# ADC_AD7761BSTZ.net
KiCad netlist of a schematic drawn in EAGLE
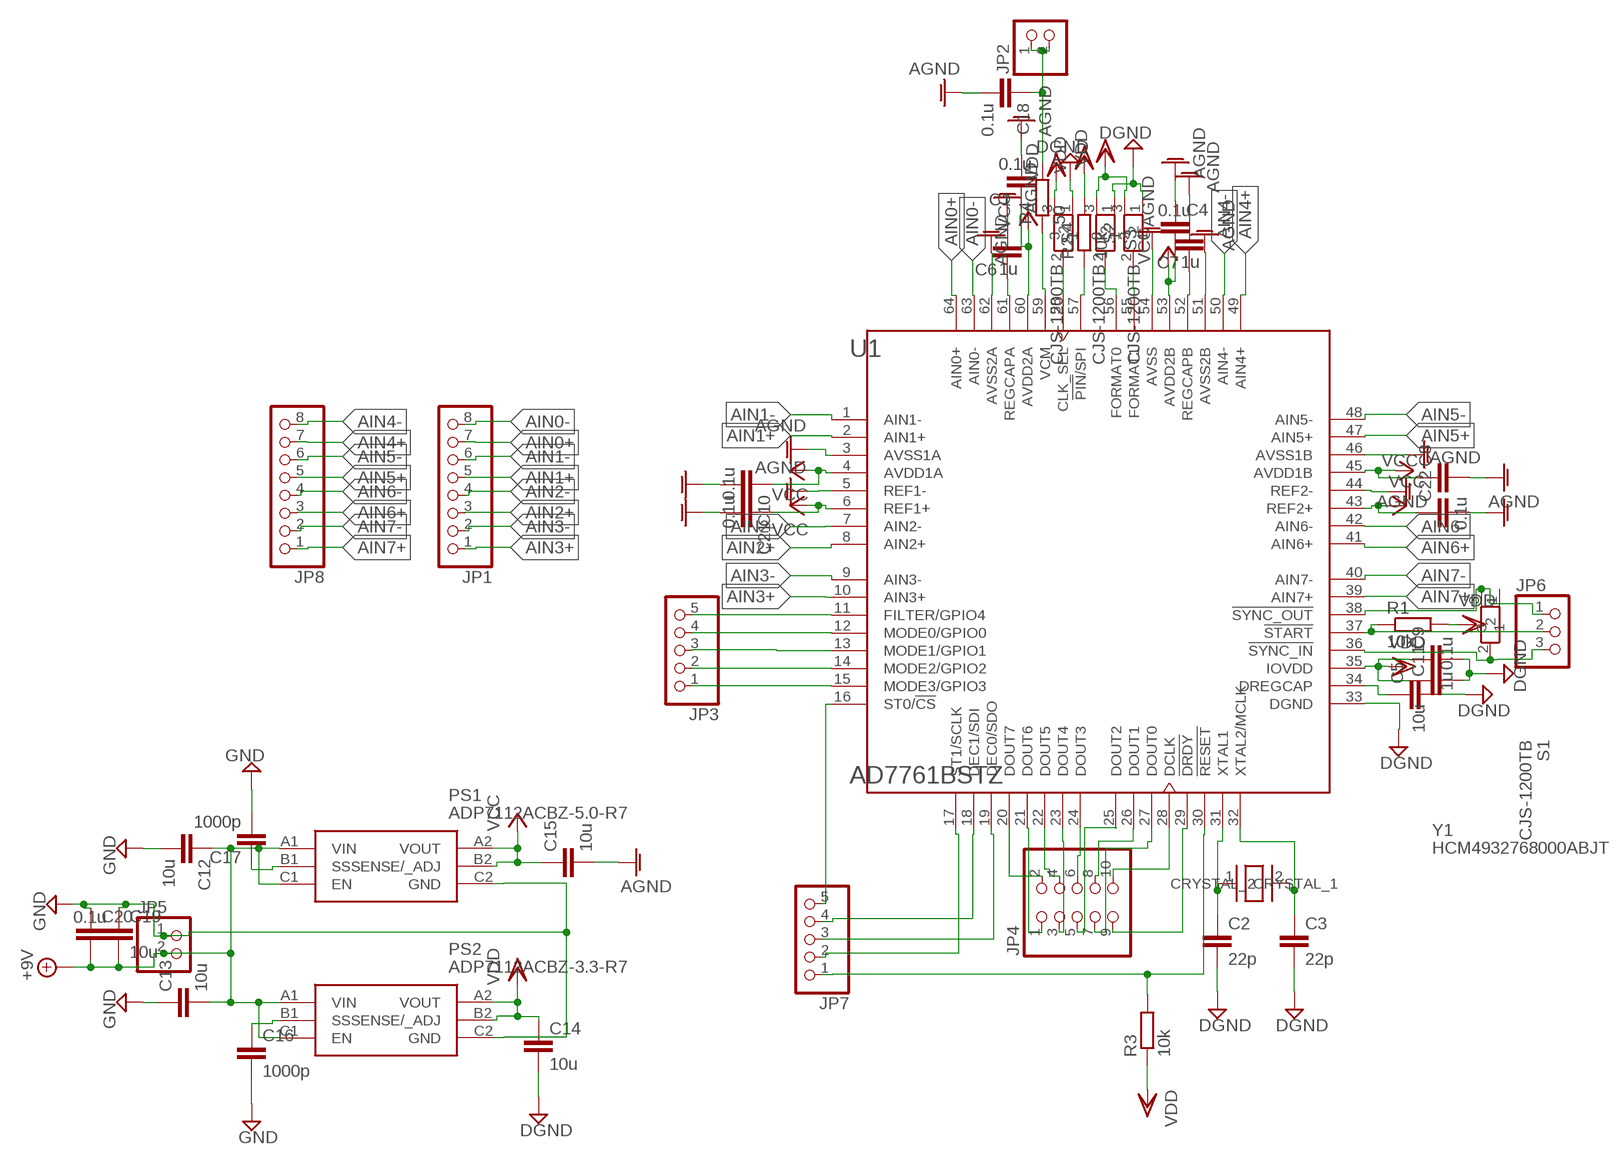
[diagram p0: schematic, sheet 1]

(export (version "E")
  (design (tool "Eeschema 10.0.6"))
  (components
    (comp (ref "C1")
      (value "0.1u")
      (footprint "eagle-import:C1608")
      (libsource (lib "eagle-import") (part "C-EUC1608"))
    )
    (comp (ref "C2")
      (value "22p")
      (footprint "eagle-import:C1608")
      (libsource (lib "eagle-import") (part "C-EUC1608"))
    )
    (comp (ref "C3")
      (value "22p")
      (footprint "eagle-import:C1608")
      (libsource (lib "eagle-import") (part "C-EUC1608"))
    )
    (comp (ref "C4")
      (value "0.1u")
      (footprint "eagle-import:C1608")
      (libsource (lib "eagle-import") (part "C-EUC1608"))
    )
    (comp (ref "C5")
      (value "10u")
      (footprint "eagle-import:C2012")
      (libsource (lib "eagle-import") (part "C-EUC2012"))
    )
    (comp (ref "C6")
      (value "1u")
      (footprint "eagle-import:C1608")
      (libsource (lib "eagle-import") (part "C-EUC1608"))
    )
    (comp (ref "C7")
      (value "1u")
      (footprint "eagle-import:C1608")
      (libsource (lib "eagle-import") (part "C-EUC1608"))
    )
    (comp (ref "C8")
      (value "0.1u")
      (footprint "eagle-import:C1608")
      (libsource (lib "eagle-import") (part "C-EUC1608"))
    )
    (comp (ref "C9")
      (value "0.1u")
      (footprint "eagle-import:C1608")
      (libsource (lib "eagle-import") (part "C-EUC1608"))
    )
    (comp (ref "C10")
      (value "0.1u")
      (footprint "eagle-import:C1608")
      (libsource (lib "eagle-import") (part "C-EUC1608"))
    )
    (comp (ref "C11")
      (value "1u")
      (footprint "eagle-import:C1608")
      (libsource (lib "eagle-import") (part "C-EUC1608"))
    )
    (comp (ref "C12")
      (value "10u")
      (footprint "eagle-import:C2012")
      (libsource (lib "eagle-import") (part "C-EUC2012"))
    )
    (comp (ref "C13")
      (value "10u")
      (footprint "eagle-import:C2012")
      (libsource (lib "eagle-import") (part "C-EUC2012"))
    )
    (comp (ref "C14")
      (value "10u")
      (footprint "eagle-import:C2012")
      (libsource (lib "eagle-import") (part "C-EUC2012"))
    )
    (comp (ref "C15")
      (value "10u")
      (footprint "eagle-import:C2012")
      (libsource (lib "eagle-import") (part "C-EUC2012"))
    )
    (comp (ref "C16")
      (value "1000p")
      (footprint "eagle-import:C1608")
      (libsource (lib "eagle-import") (part "C-EUC1608"))
    )
    (comp (ref "C17")
      (value "1000p")
      (footprint "eagle-import:C1608")
      (libsource (lib "eagle-import") (part "C-EUC1608"))
    )
    (comp (ref "C18")
      (value "0.1u")
      (footprint "eagle-import:C1608")
      (libsource (lib "eagle-import") (part "C-EUC1608"))
    )
    (comp (ref "C19")
      (value "10u")
      (footprint "eagle-import:C2012")
      (libsource (lib "eagle-import") (part "C-EUC2012"))
    )
    (comp (ref "C20")
      (value "0.1u")
      (footprint "eagle-import:C1608")
      (libsource (lib "eagle-import") (part "C-EUC1608"))
    )
    (comp (ref "C21")
      (value "0.1u")
      (footprint "eagle-import:C1608")
      (libsource (lib "eagle-import") (part "C-EUC1608"))
    )
    (comp (ref "C22")
      (value "0.1u")
      (footprint "eagle-import:C1608")
      (libsource (lib "eagle-import") (part "C-EUC1608"))
    )
    (comp (ref "JP1")
      (value "PINHD-1X8")
      (footprint "eagle-import:1X08")
      (libsource (lib "eagle-import") (part "PINHD-1X8"))
    )
    (comp (ref "JP2")
      (value "PINHD-1X2")
      (footprint "eagle-import:1X02")
      (libsource (lib "eagle-import") (part "PINHD-1X2"))
    )
    (comp (ref "JP3")
      (value "PINHD-1X5")
      (footprint "eagle-import:1X05")
      (libsource (lib "eagle-import") (part "PINHD-1X5"))
    )
    (comp (ref "JP4")
      (value "PINHD-2X5")
      (footprint "eagle-import:2X05")
      (libsource (lib "eagle-import") (part "PINHD-2X5"))
    )
    (comp (ref "JP5")
      (value "PINHD-1X2")
      (footprint "eagle-import:1X02")
      (libsource (lib "eagle-import") (part "PINHD-1X2"))
    )
    (comp (ref "JP6")
      (value "PINHD-1X3")
      (footprint "eagle-import:1X03")
      (libsource (lib "eagle-import") (part "PINHD-1X3"))
    )
    (comp (ref "JP7")
      (value "PINHD-1X5")
      (footprint "eagle-import:1X05")
      (libsource (lib "eagle-import") (part "PINHD-1X5"))
    )
    (comp (ref "JP8")
      (value "PINHD-1X8")
      (footprint "eagle-import:1X08")
      (libsource (lib "eagle-import") (part "PINHD-1X8"))
    )
    (comp (ref "PS1")
      (value "ADP7112ACBZ-5.0-R7")
      (footprint "eagle-import:BGA6C40P2X3_95X116X56")
      (fields
        (field (name "ARROW_PART_NUMBER") "ADP7112ACBZ-3.3-R7")
        (field (name "MOUSER_PART_NUMBER") "584-ADP7112ACBZ3.3R7")
      )
      (libsource (lib "eagle-import") (part "ADP7112ACBZ-3.3-R7"))
    )
    (comp (ref "PS2")
      (value "ADP7112ACBZ-3.3-R7")
      (footprint "eagle-import:BGA6C40P2X3_95X116X56")
      (fields (field (name "MOUSER_PART_NUMBER") "584-ADP7112ACBZ3.3R7"))
      (libsource (lib "eagle-import") (part "ADP7112ACBZ-3.3-R7"))
    )
    (comp (ref "R1")
      (value "10k")
      (footprint "eagle-import:R0603")
      (libsource (lib "eagle-import") (part "R-EU_R0603"))
    )
    (comp (ref "R2")
      (value "10k")
      (footprint "eagle-import:R0603")
      (libsource (lib "eagle-import") (part "R-EU_R0603"))
    )
    (comp (ref "R3")
      (value "10k")
      (footprint "eagle-import:R0603")
      (libsource (lib "eagle-import") (part "R-EU_R0603"))
    )
    (comp (ref "R4")
      (value "50")
      (footprint "eagle-import:R0603")
      (libsource (lib "eagle-import") (part "R-EU_R0603"))
    )
    (comp (ref "S1")
      (value "CJS-1200TB")
      (footprint "eagle-import:B-TYPE")
      (libsource (lib "eagle-import") (part "CJS-1200TB"))
    )
    (comp (ref "S2")
      (value "CJS-1200TB")
      (footprint "eagle-import:B-TYPE")
      (libsource (lib "eagle-import") (part "CJS-1200TB"))
    )
    (comp (ref "S3")
      (value "CJS-1200TB")
      (footprint "eagle-import:B-TYPE")
      (libsource (lib "eagle-import") (part "CJS-1200TB"))
    )
    (comp (ref "S4")
      (value "CJS-1200TB")
      (footprint "eagle-import:B-TYPE")
      (libsource (lib "eagle-import") (part "CJS-1200TB"))
    )
    (comp (ref "U1")
      (value "AD7761BSTZ")
      (footprint "eagle-import:QFP50P1200X1200X160-64N")
      (fields (field (name "MF") "Analog Devices"))
      (libsource (lib "eagle-import") (part "AD7761BSTZ"))
    )
    (comp (ref "Y1")
      (value "HCM4932768000ABJT")
      (footprint "eagle-import:HCM4932768000ABJT")
      (fields (field (name "MOUSER_PART_NUMBER") "695-HCM49-327-U"))
      (libsource (lib "eagle-import") (part "HCM4932768000ABJT"))
    )
  )
  (nets
    (net (code "1") (name "+9V") (class "Default")
      (node (ref "C12") (pin "1") (pinfunction "1_1") (pintype "passive"))
      (node (ref "C13") (pin "2") (pinfunction "2_2") (pintype "passive"))
      (node (ref "C19") (pin "2") (pinfunction "2_2") (pintype "passive"))
      (node (ref "C20") (pin "2") (pinfunction "2_2") (pintype "passive"))
      (node (ref "JP5") (pin "2") (pinfunction "2_2") (pintype "passive"))
      (node (ref "PS1") (pin "A1") (pinfunction "VIN_A1") (pintype "bidirectional"))
      (node (ref "PS1") (pin "C1") (pinfunction "EN_C1") (pintype "bidirectional"))
      (node (ref "PS2") (pin "A1") (pinfunction "VIN_A1") (pintype "bidirectional"))
      (node (ref "PS2") (pin "C1") (pinfunction "EN_C1") (pintype "bidirectional"))
    )
    (net (code "2") (name "AGND") (class "Default")
      (node (ref "C1") (pin "2") (pinfunction "2_2") (pintype "passive"))
      (node (ref "C10") (pin "2") (pinfunction "2_2") (pintype "passive"))
      (node (ref "C15") (pin "2") (pinfunction "2_2") (pintype "passive"))
      (node (ref "C18") (pin "2") (pinfunction "2_2") (pintype "passive"))
      (node (ref "C21") (pin "2") (pinfunction "2_2") (pintype "passive"))
      (node (ref "C22") (pin "2") (pinfunction "2_2") (pintype "passive"))
      (node (ref "C4") (pin "1") (pinfunction "1_1") (pintype "passive"))
      (node (ref "C6") (pin "2") (pinfunction "2_2") (pintype "passive"))
      (node (ref "C7") (pin "2") (pinfunction "2_2") (pintype "passive"))
      (node (ref "C8") (pin "2") (pinfunction "2_2") (pintype "passive"))
      (node (ref "U1") (pin "3") (pinfunction "AVSS1A_3") (pintype "power_in"))
      (node (ref "U1") (pin "44") (pinfunction "REF2-_44") (pintype "input"))
      (node (ref "U1") (pin "46") (pinfunction "AVSS1B_46") (pintype "power_in"))
      (node (ref "U1") (pin "5") (pinfunction "REF1-_5") (pintype "input"))
      (node (ref "U1") (pin "51") (pinfunction "AVSS2B_51") (pintype "power_in"))
      (node (ref "U1") (pin "54") (pinfunction "AVSS_54") (pintype "power_in"))
      (node (ref "U1") (pin "62") (pinfunction "AVSS2A_62") (pintype "power_in"))
    )
    (net (code "3") (name "AIN0+") (class "Default")
      (node (ref "JP1") (pin "7") (pinfunction "7_7") (pintype "passive"))
      (node (ref "U1") (pin "64") (pinfunction "AIN0+_64") (pintype "input"))
    )
    (net (code "4") (name "AIN0-") (class "Default")
      (node (ref "JP1") (pin "8") (pinfunction "8_8") (pintype "passive"))
      (node (ref "U1") (pin "63") (pinfunction "AIN0-_63") (pintype "input"))
    )
    (net (code "5") (name "AIN1+") (class "Default")
      (node (ref "JP1") (pin "5") (pinfunction "5_5") (pintype "passive"))
      (node (ref "U1") (pin "2") (pinfunction "AIN1+_2") (pintype "input"))
    )
    (net (code "6") (name "AIN1-") (class "Default")
      (node (ref "JP1") (pin "6") (pinfunction "6_6") (pintype "passive"))
      (node (ref "U1") (pin "1") (pinfunction "AIN1-_1") (pintype "input"))
    )
    (net (code "7") (name "AIN2+") (class "Default")
      (node (ref "JP1") (pin "3") (pinfunction "3_3") (pintype "passive"))
      (node (ref "U1") (pin "8") (pinfunction "AIN2+_8") (pintype "input"))
    )
    (net (code "8") (name "AIN2-") (class "Default")
      (node (ref "JP1") (pin "4") (pinfunction "4_4") (pintype "passive"))
      (node (ref "U1") (pin "7") (pinfunction "AIN2-_7") (pintype "input"))
    )
    (net (code "9") (name "AIN3+") (class "Default")
      (node (ref "JP1") (pin "1") (pinfunction "1_1") (pintype "passive"))
      (node (ref "U1") (pin "10") (pinfunction "AIN3+_10") (pintype "input"))
    )
    (net (code "10") (name "AIN3-") (class "Default")
      (node (ref "JP1") (pin "2") (pinfunction "2_2") (pintype "passive"))
      (node (ref "U1") (pin "9") (pinfunction "AIN3-_9") (pintype "input"))
    )
    (net (code "11") (name "AIN4+") (class "Default")
      (node (ref "JP8") (pin "7") (pinfunction "7_7") (pintype "passive"))
      (node (ref "U1") (pin "49") (pinfunction "AIN4+_49") (pintype "input"))
    )
    (net (code "12") (name "AIN4-") (class "Default")
      (node (ref "JP8") (pin "8") (pinfunction "8_8") (pintype "passive"))
      (node (ref "U1") (pin "50") (pinfunction "AIN4-_50") (pintype "input"))
    )
    (net (code "13") (name "AIN5+") (class "Default")
      (node (ref "JP8") (pin "5") (pinfunction "5_5") (pintype "passive"))
      (node (ref "U1") (pin "47") (pinfunction "AIN5+_47") (pintype "input"))
    )
    (net (code "14") (name "AIN5-") (class "Default")
      (node (ref "JP8") (pin "6") (pinfunction "6_6") (pintype "passive"))
      (node (ref "U1") (pin "48") (pinfunction "AIN5-_48") (pintype "input"))
    )
    (net (code "15") (name "AIN6+") (class "Default")
      (node (ref "JP8") (pin "3") (pinfunction "3_3") (pintype "passive"))
      (node (ref "U1") (pin "41") (pinfunction "AIN6+_41") (pintype "input"))
    )
    (net (code "16") (name "AIN6-") (class "Default")
      (node (ref "JP8") (pin "4") (pinfunction "4_4") (pintype "passive"))
      (node (ref "U1") (pin "42") (pinfunction "AIN6-_42") (pintype "input"))
    )
    (net (code "17") (name "AIN7+") (class "Default")
      (node (ref "JP8") (pin "1") (pinfunction "1_1") (pintype "passive"))
      (node (ref "U1") (pin "39") (pinfunction "AIN7+_39") (pintype "input"))
    )
    (net (code "18") (name "AIN7-") (class "Default")
      (node (ref "JP8") (pin "2") (pinfunction "2_2") (pintype "passive"))
      (node (ref "U1") (pin "40") (pinfunction "AIN7-_40") (pintype "input"))
    )
    (net (code "19") (name "DGND") (class "Default")
      (node (ref "C11") (pin "2") (pinfunction "2_2") (pintype "passive"))
      (node (ref "C14") (pin "2") (pinfunction "2_2") (pintype "passive"))
      (node (ref "C2") (pin "2") (pinfunction "2_2") (pintype "passive"))
      (node (ref "C3") (pin "2") (pinfunction "2_2") (pintype "passive"))
      (node (ref "C5") (pin "2") (pinfunction "2_2") (pintype "passive"))
      (node (ref "C9") (pin "2") (pinfunction "2_2") (pintype "passive"))
      (node (ref "S2") (pin "1") (pinfunction "1_1") (pintype "bidirectional"))
      (node (ref "S3") (pin "1") (pinfunction "1_1") (pintype "bidirectional"))
      (node (ref "S4") (pin "1") (pinfunction "1_1") (pintype "bidirectional"))
      (node (ref "U1") (pin "33") (pinfunction "DGND_33") (pintype "power_in"))
    )
    (net (code "20") (name "GND") (class "Default")
      (node (ref "C12") (pin "2") (pinfunction "2_2") (pintype "passive"))
      (node (ref "C13") (pin "1") (pinfunction "1_1") (pintype "passive"))
      (node (ref "C16") (pin "2") (pinfunction "2_2") (pintype "passive"))
      (node (ref "C17") (pin "2") (pinfunction "2_2") (pintype "passive"))
      (node (ref "C19") (pin "1") (pinfunction "1_1") (pintype "passive"))
      (node (ref "C20") (pin "1") (pinfunction "1_1") (pintype "passive"))
      (node (ref "JP5") (pin "1") (pinfunction "1_1") (pintype "passive"))
      (node (ref "PS1") (pin "C2") (pinfunction "GND_C2") (pintype "bidirectional"))
      (node (ref "PS2") (pin "C2") (pinfunction "GND_C2") (pintype "bidirectional"))
    )
    (net (code "21") (name "Net-(C18-Pad1)") (class "Default")
      (node (ref "C18") (pin "1") (pinfunction "1_1") (pintype "passive"))
      (node (ref "JP2") (pin "1") (pinfunction "1_1") (pintype "passive"))
      (node (ref "JP2") (pin "2") (pinfunction "2_2") (pintype "passive"))
      (node (ref "R4") (pin "2") (pinfunction "2_2") (pintype "passive"))
    )
    (net (code "22") (name "Net-(PS1-SS)") (class "Default")
      (node (ref "C17") (pin "1") (pinfunction "1_1") (pintype "passive"))
      (node (ref "PS1") (pin "B1") (pinfunction "SS_B1") (pintype "bidirectional"))
    )
    (net (code "23") (name "Net-(PS2-SS)") (class "Default")
      (node (ref "C16") (pin "1") (pinfunction "1_1") (pintype "passive"))
      (node (ref "PS2") (pin "B1") (pinfunction "SS_B1") (pintype "bidirectional"))
    )
    (net (code "24") (name "Net-(U1-CLK_SEL)") (class "Default")
      (node (ref "S4") (pin "2") (pinfunction "2_2") (pintype "bidirectional"))
      (node (ref "U1") (pin "58") (pinfunction "CLK_SEL_58") (pintype "input"))
    )
    (net (code "25") (name "Net-(U1-DCLK)") (class "Default")
      (node (ref "JP4") (pin "10") (pinfunction "10_10") (pintype "passive"))
      (node (ref "U1") (pin "28") (pinfunction "DCLK_28") (pintype "output"))
    )
    (net (code "26") (name "Net-(U1-DEC0{slash}SDO)") (class "Default")
      (node (ref "JP7") (pin "3") (pinfunction "3_3") (pintype "passive"))
      (node (ref "U1") (pin "19") (pinfunction "DEC0/SDO_19") (pintype "bidirectional"))
    )
    (net (code "27") (name "Net-(U1-DEC1{slash}SDI)") (class "Default")
      (node (ref "JP7") (pin "4") (pinfunction "4_4") (pintype "passive"))
      (node (ref "U1") (pin "18") (pinfunction "DEC1/SDI_18") (pintype "input"))
    )
    (net (code "28") (name "Net-(U1-DOUT0)") (class "Default")
      (node (ref "JP4") (pin "7") (pinfunction "7_7") (pintype "passive"))
      (node (ref "U1") (pin "27") (pinfunction "DOUT0_27") (pintype "output"))
    )
    (net (code "29") (name "Net-(U1-DOUT1)") (class "Default")
      (node (ref "JP4") (pin "8") (pinfunction "8_8") (pintype "passive"))
      (node (ref "U1") (pin "26") (pinfunction "DOUT1_26") (pintype "output"))
    )
    (net (code "30") (name "Net-(U1-DOUT2)") (class "Default")
      (node (ref "JP4") (pin "5") (pinfunction "5_5") (pintype "passive"))
      (node (ref "U1") (pin "25") (pinfunction "DOUT2_25") (pintype "output"))
    )
    (net (code "31") (name "Net-(U1-DOUT3)") (class "Default")
      (node (ref "JP4") (pin "6") (pinfunction "6_6") (pintype "passive"))
      (node (ref "U1") (pin "24") (pinfunction "DOUT3_24") (pintype "output"))
    )
    (net (code "32") (name "Net-(U1-DOUT4)") (class "Default")
      (node (ref "JP4") (pin "3") (pinfunction "3_3") (pintype "passive"))
      (node (ref "U1") (pin "23") (pinfunction "DOUT4_23") (pintype "output"))
    )
    (net (code "33") (name "Net-(U1-DOUT5)") (class "Default")
      (node (ref "JP4") (pin "4") (pinfunction "4_4") (pintype "passive"))
      (node (ref "U1") (pin "22") (pinfunction "DOUT5_22") (pintype "output"))
    )
    (net (code "34") (name "Net-(U1-DOUT6)") (class "Default")
      (node (ref "JP4") (pin "1") (pinfunction "1_1") (pintype "passive"))
      (node (ref "U1") (pin "21") (pinfunction "DOUT6_21") (pintype "output"))
    )
    (net (code "35") (name "Net-(U1-DOUT7)") (class "Default")
      (node (ref "JP4") (pin "2") (pinfunction "2_2") (pintype "passive"))
      (node (ref "U1") (pin "20") (pinfunction "DOUT7_20") (pintype "output"))
    )
    (net (code "36") (name "Net-(U1-DREGCAP)") (class "Default")
      (node (ref "C5") (pin "1") (pinfunction "1_1") (pintype "passive"))
      (node (ref "U1") (pin "34") (pinfunction "DREGCAP_34") (pintype "output"))
    )
    (net (code "37") (name "Net-(U1-FILTER{slash}GPIO4)") (class "Default")
      (node (ref "JP3") (pin "5") (pinfunction "5_5") (pintype "passive"))
      (node (ref "U1") (pin "11") (pinfunction "FILTER/GPIO4_11") (pintype "bidirectional"))
    )
    (net (code "38") (name "Net-(U1-FORMAT0)") (class "Default")
      (node (ref "S2") (pin "2") (pinfunction "2_2") (pintype "bidirectional"))
      (node (ref "U1") (pin "56") (pinfunction "FORMAT0_56") (pintype "input"))
    )
    (net (code "39") (name "Net-(U1-FORMAT1)") (class "Default")
      (node (ref "S3") (pin "2") (pinfunction "2_2") (pintype "bidirectional"))
      (node (ref "U1") (pin "55") (pinfunction "FORMAT1_55") (pintype "input"))
    )
    (net (code "40") (name "Net-(U1-MODE0{slash}GPIO0)") (class "Default")
      (node (ref "JP3") (pin "4") (pinfunction "4_4") (pintype "passive"))
      (node (ref "U1") (pin "12") (pinfunction "MODE0/GPIO0_12") (pintype "bidirectional"))
    )
    (net (code "41") (name "Net-(U1-MODE1{slash}GPIO1)") (class "Default")
      (node (ref "JP3") (pin "3") (pinfunction "3_3") (pintype "passive"))
      (node (ref "U1") (pin "13") (pinfunction "MODE1/GPIO1_13") (pintype "bidirectional"))
    )
    (net (code "42") (name "Net-(U1-MODE2{slash}GPIO2)") (class "Default")
      (node (ref "JP3") (pin "2") (pinfunction "2_2") (pintype "passive"))
      (node (ref "U1") (pin "14") (pinfunction "MODE2/GPIO2_14") (pintype "bidirectional"))
    )
    (net (code "43") (name "Net-(U1-MODE3{slash}GPIO3)") (class "Default")
      (node (ref "JP3") (pin "1") (pinfunction "1_1") (pintype "passive"))
      (node (ref "U1") (pin "15") (pinfunction "MODE3/GPIO3_15") (pintype "bidirectional"))
    )
    (net (code "44") (name "Net-(U1-REGCAPA)") (class "Default")
      (node (ref "C6") (pin "1") (pinfunction "1_1") (pintype "passive"))
      (node (ref "U1") (pin "61") (pinfunction "REGCAPA_61") (pintype "output"))
    )
    (net (code "45") (name "Net-(U1-REGCAPB)") (class "Default")
      (node (ref "C7") (pin "1") (pinfunction "1_1") (pintype "passive"))
      (node (ref "U1") (pin "52") (pinfunction "REGCAPB_52") (pintype "output"))
    )
    (net (code "46") (name "Net-(U1-ST0{slash}~{CS})") (class "Default")
      (node (ref "JP7") (pin "5") (pinfunction "5_5") (pintype "passive"))
      (node (ref "U1") (pin "16") (pinfunction "ST0/~{CS}_16") (pintype "input"))
    )
    (net (code "47") (name "Net-(U1-ST1{slash}SCLK)") (class "Default")
      (node (ref "JP7") (pin "2") (pinfunction "2_2") (pintype "passive"))
      (node (ref "U1") (pin "17") (pinfunction "ST1/SCLK_17") (pintype "input"))
    )
    (net (code "48") (name "Net-(U1-VCM)") (class "Default")
      (node (ref "R4") (pin "1") (pinfunction "1_1") (pintype "passive"))
      (node (ref "U1") (pin "59") (pinfunction "VCM_59") (pintype "output"))
    )
    (net (code "49") (name "Net-(U1-XTAL1)") (class "Default")
      (node (ref "C2") (pin "1") (pinfunction "1_1") (pintype "passive"))
      (node (ref "U1") (pin "31") (pinfunction "XTAL1_31") (pintype "input"))
      (node (ref "Y1") (pin "1") (pinfunction "CRYSTAL_1_1") (pintype "bidirectional"))
    )
    (net (code "50") (name "Net-(U1-XTAL2{slash}MCLK)") (class "Default")
      (node (ref "C3") (pin "1") (pinfunction "1_1") (pintype "passive"))
      (node (ref "U1") (pin "32") (pinfunction "XTAL2/MCLK_32") (pintype "input"))
      (node (ref "Y1") (pin "2") (pinfunction "CRYSTAL_2_2") (pintype "bidirectional"))
    )
    (net (code "51") (name "Net-(U1-~{DRDY})") (class "Default")
      (node (ref "JP4") (pin "9") (pinfunction "9_9") (pintype "passive"))
      (node (ref "U1") (pin "29") (pinfunction "~{DRDY}_29") (pintype "output"))
    )
    (net (code "52") (name "Net-(U1-~{PIN}{slash}SPI)") (class "Default")
      (node (ref "R2") (pin "1") (pinfunction "1_1") (pintype "passive"))
      (node (ref "U1") (pin "57") (pinfunction "~{PIN}/SPI_57") (pintype "input"))
    )
    (net (code "53") (name "Net-(U1-~{RESET})") (class "Default")
      (node (ref "JP7") (pin "1") (pinfunction "1_1") (pintype "passive"))
      (node (ref "R3") (pin "2") (pinfunction "2_2") (pintype "passive"))
      (node (ref "U1") (pin "30") (pinfunction "~{RESET}_30") (pintype "input"))
    )
    (net (code "54") (name "Net-(U1-~{START})") (class "Default")
      (node (ref "JP6") (pin "2") (pinfunction "2_2") (pintype "passive"))
      (node (ref "R1") (pin "1") (pinfunction "1_1") (pintype "passive"))
      (node (ref "U1") (pin "37") (pinfunction "~{START}_37") (pintype "input"))
    )
    (net (code "55") (name "Net-(U1-~{SYNC_IN})") (class "Default")
      (node (ref "JP6") (pin "3") (pinfunction "3_3") (pintype "passive"))
      (node (ref "S1") (pin "2") (pinfunction "2_2") (pintype "bidirectional"))
      (node (ref "U1") (pin "36") (pinfunction "~{SYNC_IN}_36") (pintype "input"))
    )
    (net (code "56") (name "Net-(U1-~{SYNC_OUT})") (class "Default")
      (node (ref "JP6") (pin "1") (pinfunction "1_1") (pintype "passive"))
      (node (ref "S1") (pin "3") (pinfunction "3_3") (pintype "bidirectional"))
      (node (ref "U1") (pin "38") (pinfunction "~{SYNC_OUT}_38") (pintype "output"))
    )
    (net (code "57") (name "VCC") (class "Default")
      (node (ref "C1") (pin "1") (pinfunction "1_1") (pintype "passive"))
      (node (ref "C10") (pin "1") (pinfunction "1_1") (pintype "passive"))
      (node (ref "C15") (pin "1") (pinfunction "1_1") (pintype "passive"))
      (node (ref "C21") (pin "1") (pinfunction "1_1") (pintype "passive"))
      (node (ref "C22") (pin "1") (pinfunction "1_1") (pintype "passive"))
      (node (ref "C4") (pin "2") (pinfunction "2_2") (pintype "passive"))
      (node (ref "C8") (pin "1") (pinfunction "1_1") (pintype "passive"))
      (node (ref "PS1") (pin "A2") (pinfunction "VOUT_A2") (pintype "bidirectional"))
      (node (ref "PS1") (pin "B2") (pinfunction "SENSE/_ADJ_B2") (pintype "bidirectional"))
      (node (ref "U1") (pin "4") (pinfunction "AVDD1A_4") (pintype "power_in"))
      (node (ref "U1") (pin "43") (pinfunction "REF2+_43") (pintype "input"))
      (node (ref "U1") (pin "45") (pinfunction "AVDD1B_45") (pintype "power_in"))
      (node (ref "U1") (pin "53") (pinfunction "AVDD2B_53") (pintype "power_in"))
      (node (ref "U1") (pin "6") (pinfunction "REF1+_6") (pintype "input"))
      (node (ref "U1") (pin "60") (pinfunction "AVDD2A_60") (pintype "power_in"))
    )
    (net (code "58") (name "VDD") (class "Default")
      (node (ref "C11") (pin "1") (pinfunction "1_1") (pintype "passive"))
      (node (ref "C14") (pin "1") (pinfunction "1_1") (pintype "passive"))
      (node (ref "C9") (pin "1") (pinfunction "1_1") (pintype "passive"))
      (node (ref "PS2") (pin "A2") (pinfunction "VOUT_A2") (pintype "bidirectional"))
      (node (ref "PS2") (pin "B2") (pinfunction "SENSE/_ADJ_B2") (pintype "bidirectional"))
      (node (ref "R1") (pin "2") (pinfunction "2_2") (pintype "passive"))
      (node (ref "R2") (pin "2") (pinfunction "2_2") (pintype "passive"))
      (node (ref "R3") (pin "1") (pinfunction "1_1") (pintype "passive"))
      (node (ref "S2") (pin "3") (pinfunction "3_3") (pintype "bidirectional"))
      (node (ref "S3") (pin "3") (pinfunction "3_3") (pintype "bidirectional"))
      (node (ref "S4") (pin "3") (pinfunction "3_3") (pintype "bidirectional"))
      (node (ref "U1") (pin "35") (pinfunction "IOVDD_35") (pintype "power_in"))
    )
    (net (code "59") (name "unconnected-(S1-Pad1)") (class "Default")
      (node (ref "S1") (pin "1") (pinfunction "1_1") (pintype "bidirectional"))
    )
  )
)
